# Bi_Dir_Circuit.net
KiCad netlist of a schematic drawn in Altium Designer
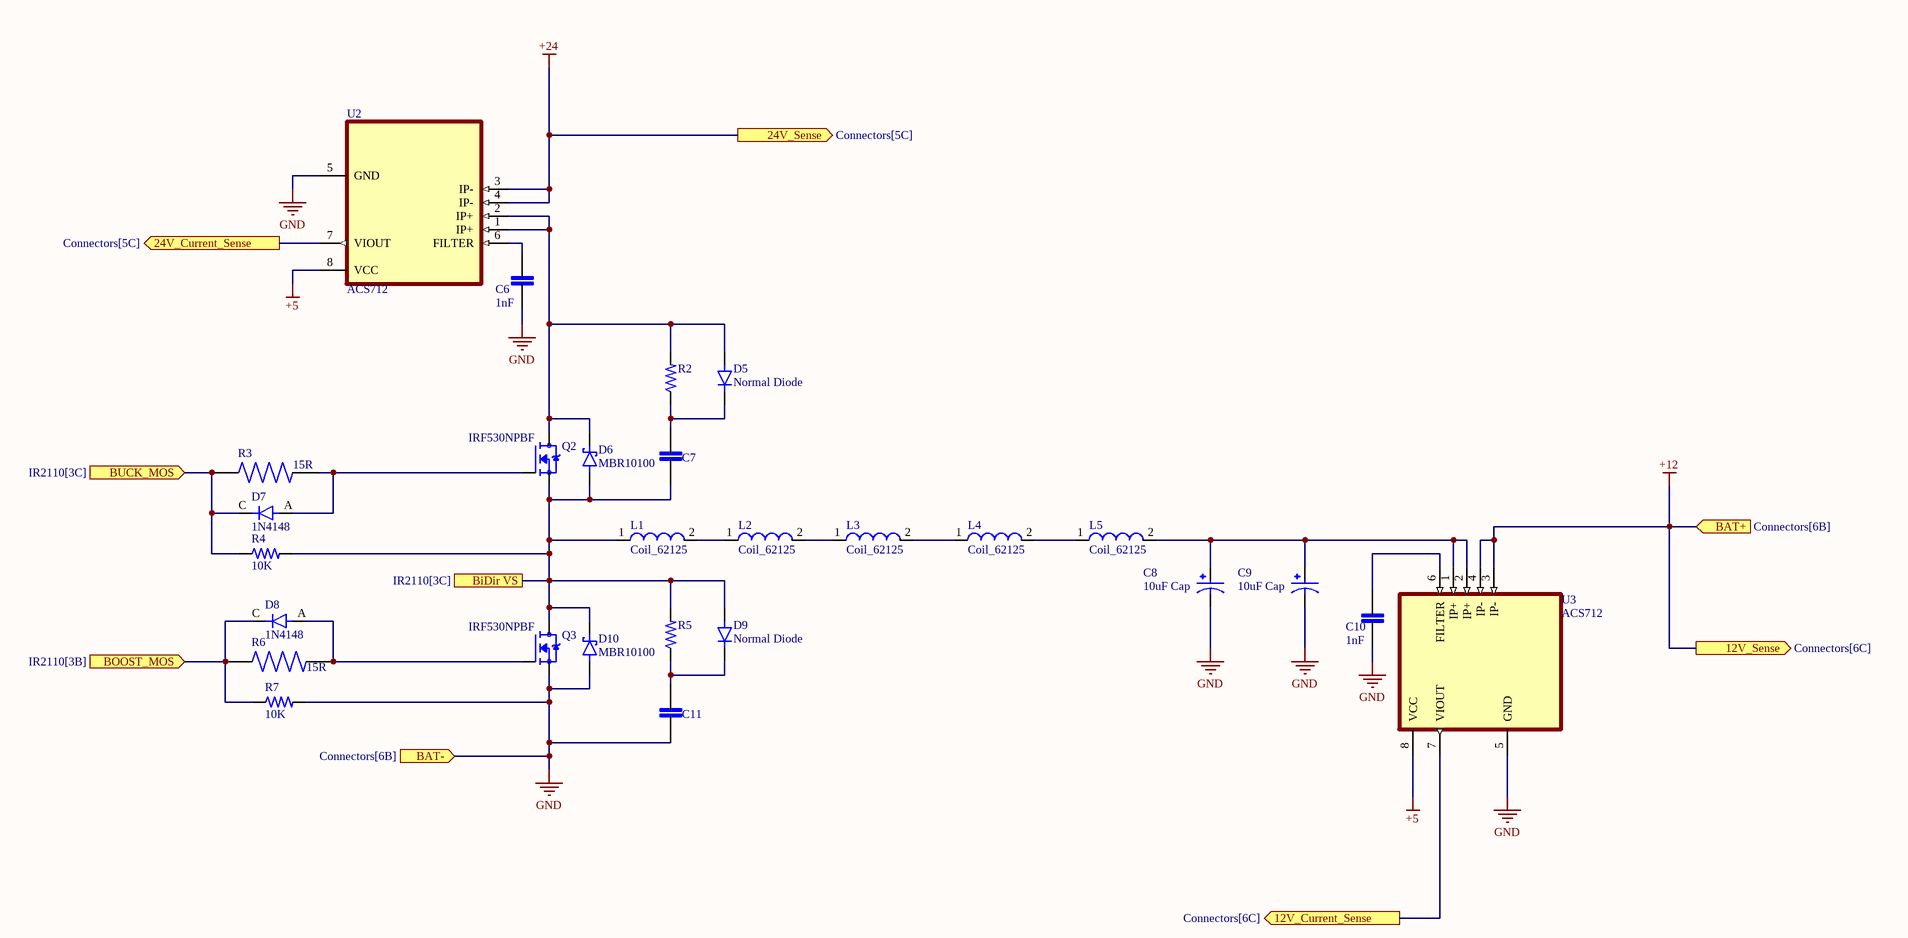
[diagram p0: Bi_Dir_Circuit.SchDoc]

(export (version "E")
  (design (tool "Eeschema 10.0.6"))
  (components
    (comp (ref "C6")
      (value "1nF")
      (footprint "Ceramic Capacitor")
      (fields (field (name "MP") "LD051A121KAB2A") (field (name "MF") "AVX"))
      (libsource (lib "Capacitors Through Hole") (part "Ceramic Capacitor"))
    )
    (comp (ref "C7")
      (value "Ceramic Capacitor")
      (footprint "Ceramic Capacitor")
      (fields (field (name "MP") "LD051A121KAB2A") (field (name "MF") "AVX"))
      (libsource (lib "Capacitors Through Hole") (part "Ceramic Capacitor"))
    )
    (comp (ref "C8")
      (value "10uF Cap")
      (footprint "2200uF_Cap")
      (description "CAP ALUM 10UF 20% 50V RADIAL")
      (fields (field (name "MP") "ECE-A1HN100UI") (field (name "MF") "Panasonic"))
      (libsource (lib "MySCH_Library") (part "10uF Cap"))
    )
    (comp (ref "C9")
      (value "10uF Cap")
      (footprint "2200uF_Cap")
      (description "CAP ALUM 10UF 20% 50V RADIAL")
      (fields (field (name "MP") "ECE-A1HN100UI") (field (name "MF") "Panasonic"))
      (libsource (lib "MySCH_Library") (part "10uF Cap"))
    )
    (comp (ref "C10")
      (value "1nF")
      (footprint "Ceramic Capacitor")
      (fields (field (name "MP") "LD051A121KAB2A") (field (name "MF") "AVX"))
      (libsource (lib "Capacitors Through Hole") (part "Ceramic Capacitor"))
    )
    (comp (ref "C11")
      (value "Ceramic Capacitor")
      (footprint "Ceramic Capacitor")
      (fields (field (name "MP") "LD051A121KAB2A") (field (name "MF") "AVX"))
      (libsource (lib "Capacitors Through Hole") (part "Ceramic Capacitor"))
    )
    (comp (ref "D5")
      (value "Normal Diode")
      (footprint "Common Trhough Hole")
      (fields (field (name "MF") "NTE Electronics, Inc.") (field (name "MP") "1N4007"))
      (libsource (lib "Diodes Through Hole") (part "Normal Diode"))
    )
    (comp (ref "D6")
      (value "MBR10100")
      (footprint "MBR10100")
      (fields (field (name "MF") "Diodes Inc.") (field (name "MP") "1N5817-T"))
      (libsource (lib "Diodes Through Hole") (part "MBR10100"))
    )
    (comp (ref "D7")
      (value "1N4148")
      (footprint "1N4007 DIODE")
      (description "Diode Standard 1000 V 1A Through Hole DO-41")
      (fields (field (name "MF") "NTE Electronics, Inc.") (field (name "MP") "1N4007"))
      (libsource (lib "MySCH_Library") (part "1N4007"))
    )
    (comp (ref "D8")
      (value "1N4148")
      (footprint "1N4007 DIODE")
      (description "Diode Standard 1000 V 1A Through Hole DO-41")
      (fields (field (name "MF") "NTE Electronics, Inc.") (field (name "MP") "1N4007"))
      (libsource (lib "MySCH_Library") (part "1N4007"))
    )
    (comp (ref "D9")
      (value "Normal Diode")
      (footprint "Common Trhough Hole")
      (fields (field (name "MF") "NTE Electronics, Inc.") (field (name "MP") "1N4007"))
      (libsource (lib "Diodes Through Hole") (part "Normal Diode"))
    )
    (comp (ref "D10")
      (value "MBR10100")
      (footprint "MBR10100")
      (fields (field (name "MF") "Diodes Inc.") (field (name "MP") "1N5817-T"))
      (libsource (lib "Diodes Through Hole") (part "MBR10100"))
    )
    (comp (ref "L1")
      (value "Coil_62125")
      (footprint "Coil 65125")
      (description "Inductor Power Wirewound 470uH 10% 1KHz 25Q-Factor Ferrite 210mA 3.3Ohm DCR T/R")
      (fields (field (name "DIGI-KEY_PART_NUMBER") "SDR0604-471KLCT-ND") (field (name "MF") "Bourns"))
      (libsource (lib "MySCH_Library") (part "Coil_62125"))
    )
    (comp (ref "L2")
      (value "Coil_62125")
      (footprint "Coil 65125")
      (description "Inductor Power Wirewound 470uH 10% 1KHz 25Q-Factor Ferrite 210mA 3.3Ohm DCR T/R")
      (fields (field (name "DIGI-KEY_PART_NUMBER") "SDR0604-471KLCT-ND") (field (name "MF") "Bourns"))
      (libsource (lib "MySCH_Library") (part "Coil_62125"))
    )
    (comp (ref "L3")
      (value "Coil_62125")
      (footprint "Coil 65125")
      (description "Inductor Power Wirewound 470uH 10% 1KHz 25Q-Factor Ferrite 210mA 3.3Ohm DCR T/R")
      (fields (field (name "DIGI-KEY_PART_NUMBER") "SDR0604-471KLCT-ND") (field (name "MF") "Bourns"))
      (libsource (lib "MySCH_Library") (part "Coil_62125"))
    )
    (comp (ref "L4")
      (value "Coil_62125")
      (footprint "Coil 65125")
      (description "Inductor Power Wirewound 470uH 10% 1KHz 25Q-Factor Ferrite 210mA 3.3Ohm DCR T/R")
      (fields (field (name "DIGI-KEY_PART_NUMBER") "SDR0604-471KLCT-ND") (field (name "MF") "Bourns"))
      (libsource (lib "MySCH_Library") (part "Coil_62125"))
    )
    (comp (ref "L5")
      (value "Coil_62125")
      (footprint "Coil 65125")
      (description "Inductor Power Wirewound 470uH 10% 1KHz 25Q-Factor Ferrite 210mA 3.3Ohm DCR T/R")
      (fields (field (name "DIGI-KEY_PART_NUMBER") "SDR0604-471KLCT-ND") (field (name "MF") "Bourns"))
      (libsource (lib "MySCH_Library") (part "Coil_62125"))
    )
    (comp (ref "Q2")
      (value "IRF530NPBF")
      (footprint "IRF530N")
      (fields (field (name "MF") "Infineon Technologies"))
      (libsource (lib "MySCH_Library") (part "IRF530NPBF"))
    )
    (comp (ref "Q3")
      (value "IRF530NPBF")
      (footprint "IRF530N")
      (fields (field (name "MF") "Infineon Technologies"))
      (libsource (lib "MySCH_Library") (part "IRF530NPBF"))
    )
    (comp (ref "R2")
      (value "Resistor")
      (footprint "Resistor_Through Hole")
      (fields
        (field (name "MP") "2-2176053-0")
        (field (name "TOLERANCE") "1%")
        (field (name "MF") "TE Connectivity")
      )
      (libsource (lib "Resistors Through Hole") (part "Resistor"))
    )
    (comp (ref "R3")
      (value "15R")
      (footprint "Resistor_Through Hole")
      (description "1.02 Ohms Â±1% 0.25W, 1/4W Through Hole Resistor Axial Metal Film")
      (fields (field (name "MP") "MFR-25FTE52-1R") (field (name "MF") "Yageo"))
      (libsource (lib "MySCH_Library") (part "Resistor_Through Hole"))
    )
    (comp (ref "R4")
      (value "10K")
      (footprint "Resistor_Through Hole")
      (fields
        (field (name "MP") "2-2176053-0")
        (field (name "TOLERANCE") "1%")
        (field (name "MF") "TE Connectivity")
      )
      (libsource (lib "Resistors Through Hole") (part "Resistor"))
    )
    (comp (ref "R5")
      (value "Resistor")
      (footprint "Resistor_Through Hole")
      (fields
        (field (name "MP") "2-2176053-0")
        (field (name "TOLERANCE") "1%")
        (field (name "MF") "TE Connectivity")
      )
      (libsource (lib "Resistors Through Hole") (part "Resistor"))
    )
    (comp (ref "R6")
      (value "15R")
      (footprint "Resistor_Through Hole")
      (description "1.02 Ohms Â±1% 0.25W, 1/4W Through Hole Resistor Axial Metal Film")
      (fields (field (name "MP") "MFR-25FTE52-1R") (field (name "MF") "Yageo"))
      (libsource (lib "MySCH_Library") (part "Resistor_Through Hole"))
    )
    (comp (ref "R7")
      (value "10K")
      (footprint "Resistor_Through Hole")
      (fields
        (field (name "MP") "2-2176053-0")
        (field (name "TOLERANCE") "1%")
        (field (name "MF") "TE Connectivity")
      )
      (libsource (lib "Resistors Through Hole") (part "Resistor"))
    )
    (comp (ref "U2")
      (value "ACS712")
      (footprint "ACS712")
      (description "Current Sensor 5A 1 Channel Hall Effect, Open Loop Bidirectional 8-SOIC (0.154, 3.90mm Width)")
      (fields (field (name "MP") "ACS712ELCTR-05B-T") (field (name "MF") "Allegro MicroSystems LLC"))
      (libsource (lib "Hall Current Sensor") (part "ACS712"))
    )
    (comp (ref "U3")
      (value "ACS712")
      (footprint "ACS712")
      (description "Current Sensor 5A 1 Channel Hall Effect, Open Loop Bidirectional 8-SOIC (0.154, 3.90mm Width)")
      (fields (field (name "MP") "ACS712ELCTR-05B-T") (field (name "MF") "Allegro MicroSystems LLC"))
      (libsource (lib "Hall Current Sensor") (part "ACS712"))
    )
  )
  (nets
    (net (code "1") (name "+5") (class "Default")
      (node (ref "U2") (pin "8") (pinfunction "VCC_8") (pintype "power_in"))
      (node (ref "U3") (pin "8") (pinfunction "VCC_8") (pintype "power_in"))
    )
    (net (code "2") (name "+12") (class "Default")
      (node (ref "U3") (pin "3") (pinfunction "IP-_3") (pintype "input"))
      (node (ref "U3") (pin "4") (pinfunction "IP-_4") (pintype "input"))
    )
    (net (code "3") (name "+24") (class "Default")
      (node (ref "U2") (pin "3") (pinfunction "IP-_3") (pintype "input"))
      (node (ref "U2") (pin "4") (pinfunction "IP-_4") (pintype "input"))
    )
    (net (code "4") (name "/12V_Current_Sense") (class "Default")
      (node (ref "U3") (pin "7") (pinfunction "VIOUT_7") (pintype "output"))
    )
    (net (code "5") (name "/24V_Current_Sense") (class "Default")
      (node (ref "U2") (pin "7") (pinfunction "VIOUT_7") (pintype "output"))
    )
    (net (code "6") (name "/BOOST_MOS") (class "Default")
      (node (ref "D8") (pin "C") (pinfunction "C_C") (pintype "passive"))
      (node (ref "R6") (pin "1") (pinfunction "1_1") (pintype "passive"))
      (node (ref "R7") (pin "1") (pinfunction "1_1") (pintype "passive"))
    )
    (net (code "7") (name "/BUCK_MOS") (class "Default")
      (node (ref "D7") (pin "C") (pinfunction "C_C") (pintype "passive"))
      (node (ref "R3") (pin "1") (pinfunction "1_1") (pintype "passive"))
      (node (ref "R4") (pin "1") (pinfunction "1_1") (pintype "passive"))
    )
    (net (code "8") (name "/BiDir VS") (class "Default")
      (node (ref "C7") (pin "1") (pinfunction "1_1") (pintype "passive"))
      (node (ref "D10") (pin "1") (pinfunction "K_1") (pintype "passive"))
      (node (ref "D6") (pin "3") (pinfunction "A_3") (pintype "passive"))
      (node (ref "D9") (pin "2") (pinfunction "A_2") (pintype "passive"))
      (node (ref "L1") (pin "1") (pinfunction "1_1") (pintype "passive"))
      (node (ref "Q2") (pin "3") (pinfunction "S_3") (pintype "passive"))
      (node (ref "Q3") (pin "2") (pinfunction "D_2") (pintype "passive"))
      (node (ref "R4") (pin "2") (pinfunction "2_2") (pintype "passive"))
      (node (ref "R5") (pin "2") (pinfunction "2_2") (pintype "passive"))
    )
    (net (code "9") (name "GND") (class "Default")
      (node (ref "C10") (pin "1") (pinfunction "1_1") (pintype "passive"))
      (node (ref "C11") (pin "1") (pinfunction "1_1") (pintype "passive"))
      (node (ref "C6") (pin "1") (pinfunction "1_1") (pintype "passive"))
      (node (ref "C8") (pin "N") (pinfunction "N_N") (pintype "passive"))
      (node (ref "C9") (pin "N") (pinfunction "N_N") (pintype "passive"))
      (node (ref "D10") (pin "3") (pinfunction "A_3") (pintype "passive"))
      (node (ref "Q3") (pin "3") (pinfunction "S_3") (pintype "passive"))
      (node (ref "R7") (pin "2") (pinfunction "2_2") (pintype "passive"))
      (node (ref "U2") (pin "5") (pinfunction "GND_5") (pintype "power_in"))
      (node (ref "U3") (pin "5") (pinfunction "GND_5") (pintype "power_in"))
    )
    (net (code "10") (name "Net-(C8-PadP)") (class "Default")
      (node (ref "C8") (pin "P") (pinfunction "P_P") (pintype "passive"))
      (node (ref "C9") (pin "P") (pinfunction "P_P") (pintype "passive"))
      (node (ref "L5") (pin "2") (pinfunction "2_2") (pintype "passive"))
      (node (ref "U3") (pin "1") (pinfunction "IP+_1") (pintype "input"))
      (node (ref "U3") (pin "2") (pinfunction "IP+_2") (pintype "input"))
    )
    (net (code "11") (name "Net-(D5-A)") (class "Default")
      (node (ref "D5") (pin "2") (pinfunction "A_2") (pintype "passive"))
      (node (ref "D6") (pin "1") (pinfunction "K_1") (pintype "passive"))
      (node (ref "Q2") (pin "2") (pinfunction "D_2") (pintype "passive"))
      (node (ref "R2") (pin "2") (pinfunction "2_2") (pintype "passive"))
      (node (ref "U2") (pin "1") (pinfunction "IP+_1") (pintype "input"))
      (node (ref "U2") (pin "2") (pinfunction "IP+_2") (pintype "input"))
    )
    (net (code "12") (name "Net-(D5-K)") (class "Default")
      (node (ref "C7") (pin "2") (pinfunction "2_2") (pintype "passive"))
      (node (ref "D5") (pin "1") (pinfunction "K_1") (pintype "passive"))
      (node (ref "R2") (pin "1") (pinfunction "1_1") (pintype "passive"))
    )
    (net (code "13") (name "Net-(D9-K)") (class "Default")
      (node (ref "C11") (pin "2") (pinfunction "2_2") (pintype "passive"))
      (node (ref "D9") (pin "1") (pinfunction "K_1") (pintype "passive"))
      (node (ref "R5") (pin "1") (pinfunction "1_1") (pintype "passive"))
    )
    (net (code "14") (name "Net-(L1-Pad2)") (class "Default")
      (node (ref "L1") (pin "2") (pinfunction "2_2") (pintype "passive"))
      (node (ref "L2") (pin "1") (pinfunction "1_1") (pintype "passive"))
    )
    (net (code "15") (name "Net-(L2-Pad2)") (class "Default")
      (node (ref "L2") (pin "2") (pinfunction "2_2") (pintype "passive"))
      (node (ref "L3") (pin "1") (pinfunction "1_1") (pintype "passive"))
    )
    (net (code "16") (name "Net-(L3-Pad2)") (class "Default")
      (node (ref "L3") (pin "2") (pinfunction "2_2") (pintype "passive"))
      (node (ref "L4") (pin "1") (pinfunction "1_1") (pintype "passive"))
    )
    (net (code "17") (name "Net-(L4-Pad2)") (class "Default")
      (node (ref "L4") (pin "2") (pinfunction "2_2") (pintype "passive"))
      (node (ref "L5") (pin "1") (pinfunction "1_1") (pintype "passive"))
    )
    (net (code "18") (name "Net-(Q2-G)") (class "Default")
      (node (ref "D7") (pin "A") (pinfunction "A_A") (pintype "passive"))
      (node (ref "Q2") (pin "1") (pinfunction "G_1") (pintype "passive"))
      (node (ref "R3") (pin "2") (pinfunction "2_2") (pintype "passive"))
    )
    (net (code "19") (name "Net-(Q3-G)") (class "Default")
      (node (ref "D8") (pin "A") (pinfunction "A_A") (pintype "passive"))
      (node (ref "Q3") (pin "1") (pinfunction "G_1") (pintype "passive"))
      (node (ref "R6") (pin "2") (pinfunction "2_2") (pintype "passive"))
    )
    (net (code "20") (name "Net-(U2-FILTER)") (class "Default")
      (node (ref "C6") (pin "2") (pinfunction "2_2") (pintype "passive"))
      (node (ref "U2") (pin "6") (pinfunction "FILTER_6") (pintype "input"))
    )
    (net (code "21") (name "Net-(U3-FILTER)") (class "Default")
      (node (ref "C10") (pin "2") (pinfunction "2_2") (pintype "passive"))
      (node (ref "U3") (pin "6") (pinfunction "FILTER_6") (pintype "input"))
    )
  )
)
